# amp_pt2322_v_1_0.net
KiCad netlist of a schematic drawn in EAGLE
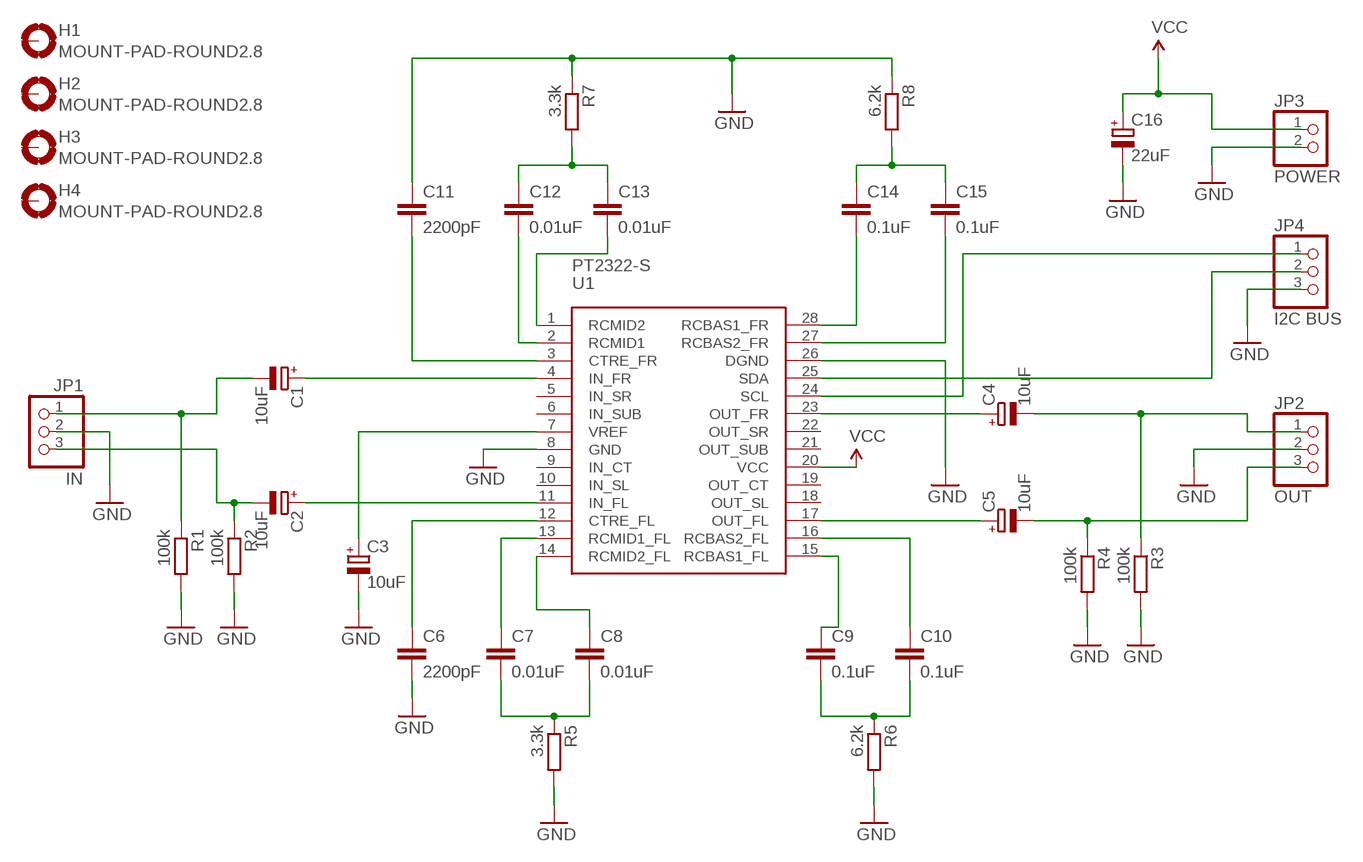
[diagram p0: schematic, sheet 1]

(export (version "E")
  (design (tool "Eeschema 10.0.6"))
  (components
    (comp (ref "C1")
      (value "10uF")
      (footprint "eagle-import:SMC_B")
      (libsource (lib "eagle-import") (part "CPOL-EUSMCB"))
    )
    (comp (ref "C2")
      (value "10uF")
      (footprint "eagle-import:SMC_B")
      (libsource (lib "eagle-import") (part "CPOL-EUSMCB"))
    )
    (comp (ref "C3")
      (value "10uF")
      (footprint "eagle-import:SMC_B")
      (libsource (lib "eagle-import") (part "CPOL-EUSMCB"))
    )
    (comp (ref "C4")
      (value "10uF")
      (footprint "eagle-import:SMC_B")
      (libsource (lib "eagle-import") (part "CPOL-EUSMCB"))
    )
    (comp (ref "C5")
      (value "10uF")
      (footprint "eagle-import:SMC_B")
      (libsource (lib "eagle-import") (part "CPOL-EUSMCB"))
    )
    (comp (ref "C6")
      (value "2200pF")
      (footprint "eagle-import:C0805K")
      (libsource (lib "eagle-import") (part "C-EUC0805K"))
    )
    (comp (ref "C7")
      (value "0.01uF")
      (footprint "eagle-import:C0805K")
      (libsource (lib "eagle-import") (part "C-EUC0805K"))
    )
    (comp (ref "C8")
      (value "0.01uF")
      (footprint "eagle-import:C0805K")
      (libsource (lib "eagle-import") (part "C-EUC0805K"))
    )
    (comp (ref "C9")
      (value "0.1uF")
      (footprint "eagle-import:C0805K")
      (libsource (lib "eagle-import") (part "C-EUC0805K"))
    )
    (comp (ref "C10")
      (value "0.1uF")
      (footprint "eagle-import:C0805K")
      (libsource (lib "eagle-import") (part "C-EUC0805K"))
    )
    (comp (ref "C11")
      (value "2200pF")
      (footprint "eagle-import:C0805K")
      (libsource (lib "eagle-import") (part "C-EUC0805K"))
    )
    (comp (ref "C12")
      (value "0.01uF")
      (footprint "eagle-import:C0805K")
      (libsource (lib "eagle-import") (part "C-EUC0805K"))
    )
    (comp (ref "C13")
      (value "0.01uF")
      (footprint "eagle-import:C0805K")
      (libsource (lib "eagle-import") (part "C-EUC0805K"))
    )
    (comp (ref "C14")
      (value "0.1uF")
      (footprint "eagle-import:C0805K")
      (libsource (lib "eagle-import") (part "C-EUC0805K"))
    )
    (comp (ref "C15")
      (value "0.1uF")
      (footprint "eagle-import:C0805K")
      (libsource (lib "eagle-import") (part "C-EUC0805K"))
    )
    (comp (ref "C16")
      (value "22uF")
      (footprint "eagle-import:SMC_B")
      (libsource (lib "eagle-import") (part "CPOL-EUSMCB"))
    )
    (comp (ref "H1")
      (value "MOUNT-PAD-ROUND2.8")
      (footprint "eagle-import:2,8-PAD")
      (libsource (lib "eagle-import") (part "MOUNT-PAD-ROUND2.8"))
    )
    (comp (ref "H2")
      (value "MOUNT-PAD-ROUND2.8")
      (footprint "eagle-import:2,8-PAD")
      (libsource (lib "eagle-import") (part "MOUNT-PAD-ROUND2.8"))
    )
    (comp (ref "H3")
      (value "MOUNT-PAD-ROUND2.8")
      (footprint "eagle-import:2,8-PAD")
      (libsource (lib "eagle-import") (part "MOUNT-PAD-ROUND2.8"))
    )
    (comp (ref "H4")
      (value "MOUNT-PAD-ROUND2.8")
      (footprint "eagle-import:2,8-PAD")
      (libsource (lib "eagle-import") (part "MOUNT-PAD-ROUND2.8"))
    )
    (comp (ref "JP1")
      (value "IN")
      (footprint "eagle-import:1X03")
      (libsource (lib "eagle-import") (part "PINHD-1X3"))
    )
    (comp (ref "JP2")
      (value "OUT")
      (footprint "eagle-import:1X03")
      (libsource (lib "eagle-import") (part "PINHD-1X3"))
    )
    (comp (ref "JP3")
      (value "POWER")
      (footprint "eagle-import:1X02")
      (libsource (lib "eagle-import") (part "PINHD-1X2"))
    )
    (comp (ref "JP4")
      (value "I2C BUS")
      (footprint "eagle-import:1X03")
      (libsource (lib "eagle-import") (part "PINHD-1X3"))
    )
    (comp (ref "R1")
      (value "100k")
      (footprint "eagle-import:R0805")
      (libsource (lib "eagle-import") (part "R-EU_R0805"))
    )
    (comp (ref "R2")
      (value "100k")
      (footprint "eagle-import:R0805")
      (libsource (lib "eagle-import") (part "R-EU_R0805"))
    )
    (comp (ref "R3")
      (value "100k")
      (footprint "eagle-import:R0805")
      (libsource (lib "eagle-import") (part "R-EU_R0805"))
    )
    (comp (ref "R4")
      (value "100k")
      (footprint "eagle-import:R0805")
      (libsource (lib "eagle-import") (part "R-EU_R0805"))
    )
    (comp (ref "R5")
      (value "3.3k")
      (footprint "eagle-import:R0805")
      (libsource (lib "eagle-import") (part "R-EU_R0805"))
    )
    (comp (ref "R6")
      (value "6.2k")
      (footprint "eagle-import:R0805")
      (libsource (lib "eagle-import") (part "R-EU_R0805"))
    )
    (comp (ref "R7")
      (value "3.3k")
      (footprint "eagle-import:R0805")
      (libsource (lib "eagle-import") (part "R-EU_R0805"))
    )
    (comp (ref "R8")
      (value "6.2k")
      (footprint "eagle-import:R0805")
      (libsource (lib "eagle-import") (part "R-EU_R0805"))
    )
    (comp (ref "U1")
      (value "PT2322-S")
      (footprint "eagle-import:SOP28")
      (libsource (lib "eagle-import") (part "PT2322-S"))
    )
  )
  (nets
    (net (code "1") (name "GND") (class "Default")
      (node (ref "C11") (pin "1") (pinfunction "1_1") (pintype "passive"))
      (node (ref "C16") (pin "-") (pinfunction "-_-") (pintype "passive"))
      (node (ref "C3") (pin "-") (pinfunction "-_-") (pintype "passive"))
      (node (ref "C6") (pin "2") (pinfunction "2_2") (pintype "passive"))
      (node (ref "JP1") (pin "2") (pinfunction "2_2") (pintype "passive"))
      (node (ref "JP2") (pin "2") (pinfunction "2_2") (pintype "passive"))
      (node (ref "JP3") (pin "2") (pinfunction "2_2") (pintype "passive"))
      (node (ref "JP4") (pin "3") (pinfunction "3_3") (pintype "passive"))
      (node (ref "R1") (pin "2") (pinfunction "2_2") (pintype "passive"))
      (node (ref "R2") (pin "2") (pinfunction "2_2") (pintype "passive"))
      (node (ref "R3") (pin "2") (pinfunction "2_2") (pintype "passive"))
      (node (ref "R4") (pin "2") (pinfunction "2_2") (pintype "passive"))
      (node (ref "R5") (pin "2") (pinfunction "2_2") (pintype "passive"))
      (node (ref "R6") (pin "2") (pinfunction "2_2") (pintype "passive"))
      (node (ref "R7") (pin "1") (pinfunction "1_1") (pintype "passive"))
      (node (ref "R8") (pin "1") (pinfunction "1_1") (pintype "passive"))
      (node (ref "U1") (pin "26") (pinfunction "DGND_26") (pintype "power_in"))
      (node (ref "U1") (pin "8") (pinfunction "GND_8") (pintype "power_in"))
    )
    (net (code "2") (name "Net-(C1-Pad-)") (class "Default")
      (node (ref "C1") (pin "-") (pinfunction "-_-") (pintype "passive"))
      (node (ref "JP1") (pin "1") (pinfunction "1_1") (pintype "passive"))
      (node (ref "R1") (pin "1") (pinfunction "1_1") (pintype "passive"))
    )
    (net (code "3") (name "Net-(C2-Pad-)") (class "Default")
      (node (ref "C2") (pin "-") (pinfunction "-_-") (pintype "passive"))
      (node (ref "JP1") (pin "3") (pinfunction "3_3") (pintype "passive"))
      (node (ref "R2") (pin "1") (pinfunction "1_1") (pintype "passive"))
    )
    (net (code "4") (name "Net-(C4-Pad-)") (class "Default")
      (node (ref "C4") (pin "-") (pinfunction "-_-") (pintype "passive"))
      (node (ref "JP2") (pin "1") (pinfunction "1_1") (pintype "passive"))
      (node (ref "R3") (pin "1") (pinfunction "1_1") (pintype "passive"))
    )
    (net (code "5") (name "Net-(C5-Pad-)") (class "Default")
      (node (ref "C5") (pin "-") (pinfunction "-_-") (pintype "passive"))
      (node (ref "JP2") (pin "3") (pinfunction "3_3") (pintype "passive"))
      (node (ref "R4") (pin "1") (pinfunction "1_1") (pintype "passive"))
    )
    (net (code "6") (name "Net-(C7-Pad2)") (class "Default")
      (node (ref "C7") (pin "2") (pinfunction "2_2") (pintype "passive"))
      (node (ref "C8") (pin "2") (pinfunction "2_2") (pintype "passive"))
      (node (ref "R5") (pin "1") (pinfunction "1_1") (pintype "passive"))
    )
    (net (code "7") (name "Net-(C10-Pad2)") (class "Default")
      (node (ref "C10") (pin "2") (pinfunction "2_2") (pintype "passive"))
      (node (ref "C9") (pin "2") (pinfunction "2_2") (pintype "passive"))
      (node (ref "R6") (pin "1") (pinfunction "1_1") (pintype "passive"))
    )
    (net (code "8") (name "Net-(C12-Pad1)") (class "Default")
      (node (ref "C12") (pin "1") (pinfunction "1_1") (pintype "passive"))
      (node (ref "C13") (pin "1") (pinfunction "1_1") (pintype "passive"))
      (node (ref "R7") (pin "2") (pinfunction "2_2") (pintype "passive"))
    )
    (net (code "9") (name "Net-(C14-Pad1)") (class "Default")
      (node (ref "C14") (pin "1") (pinfunction "1_1") (pintype "passive"))
      (node (ref "C15") (pin "1") (pinfunction "1_1") (pintype "passive"))
      (node (ref "R8") (pin "2") (pinfunction "2_2") (pintype "passive"))
    )
    (net (code "10") (name "Net-(U1-CTRE_FL)") (class "Default")
      (node (ref "C6") (pin "1") (pinfunction "1_1") (pintype "passive"))
      (node (ref "U1") (pin "12") (pinfunction "CTRE_FL_12") (pintype "bidirectional"))
    )
    (net (code "11") (name "Net-(U1-CTRE_FR)") (class "Default")
      (node (ref "C11") (pin "2") (pinfunction "2_2") (pintype "passive"))
      (node (ref "U1") (pin "3") (pinfunction "CTRE_FR_3") (pintype "bidirectional"))
    )
    (net (code "12") (name "Net-(U1-IN_FL)") (class "Default")
      (node (ref "C2") (pin "+") (pinfunction "+_+") (pintype "passive"))
      (node (ref "U1") (pin "11") (pinfunction "IN_FL_11") (pintype "input"))
    )
    (net (code "13") (name "Net-(U1-IN_FR)") (class "Default")
      (node (ref "C1") (pin "+") (pinfunction "+_+") (pintype "passive"))
      (node (ref "U1") (pin "4") (pinfunction "IN_FR_4") (pintype "input"))
    )
    (net (code "14") (name "Net-(U1-OUT_FL)") (class "Default")
      (node (ref "C5") (pin "+") (pinfunction "+_+") (pintype "passive"))
      (node (ref "U1") (pin "17") (pinfunction "OUT_FL_17") (pintype "output"))
    )
    (net (code "15") (name "Net-(U1-OUT_FR)") (class "Default")
      (node (ref "C4") (pin "+") (pinfunction "+_+") (pintype "passive"))
      (node (ref "U1") (pin "23") (pinfunction "OUT_FR_23") (pintype "output"))
    )
    (net (code "16") (name "Net-(U1-RCBAS1_FL)") (class "Default")
      (node (ref "C9") (pin "1") (pinfunction "1_1") (pintype "passive"))
      (node (ref "U1") (pin "15") (pinfunction "RCBAS1_FL_15") (pintype "bidirectional"))
    )
    (net (code "17") (name "Net-(U1-RCBAS1_FR)") (class "Default")
      (node (ref "C14") (pin "2") (pinfunction "2_2") (pintype "passive"))
      (node (ref "U1") (pin "28") (pinfunction "RCBAS1_FR_28") (pintype "bidirectional"))
    )
    (net (code "18") (name "Net-(U1-RCBAS2_FL)") (class "Default")
      (node (ref "C10") (pin "1") (pinfunction "1_1") (pintype "passive"))
      (node (ref "U1") (pin "16") (pinfunction "RCBAS2_FL_16") (pintype "bidirectional"))
    )
    (net (code "19") (name "Net-(U1-RCBAS2_FR)") (class "Default")
      (node (ref "C15") (pin "2") (pinfunction "2_2") (pintype "passive"))
      (node (ref "U1") (pin "27") (pinfunction "RCBAS2_FR_27") (pintype "bidirectional"))
    )
    (net (code "20") (name "Net-(U1-RCMID1)") (class "Default")
      (node (ref "C12") (pin "2") (pinfunction "2_2") (pintype "passive"))
      (node (ref "U1") (pin "2") (pinfunction "RCMID1_2") (pintype "bidirectional"))
    )
    (net (code "21") (name "Net-(U1-RCMID1_FL)") (class "Default")
      (node (ref "C7") (pin "1") (pinfunction "1_1") (pintype "passive"))
      (node (ref "U1") (pin "13") (pinfunction "RCMID1_FL_13") (pintype "bidirectional"))
    )
    (net (code "22") (name "Net-(U1-RCMID2)") (class "Default")
      (node (ref "C13") (pin "2") (pinfunction "2_2") (pintype "passive"))
      (node (ref "U1") (pin "1") (pinfunction "RCMID2_1") (pintype "bidirectional"))
    )
    (net (code "23") (name "Net-(U1-RCMID2_FL)") (class "Default")
      (node (ref "C8") (pin "1") (pinfunction "1_1") (pintype "passive"))
      (node (ref "U1") (pin "14") (pinfunction "RCMID2_FL_14") (pintype "bidirectional"))
    )
    (net (code "24") (name "Net-(U1-SCL)") (class "Default")
      (node (ref "JP4") (pin "1") (pinfunction "1_1") (pintype "passive"))
      (node (ref "U1") (pin "24") (pinfunction "SCL_24") (pintype "bidirectional"))
    )
    (net (code "25") (name "Net-(U1-SDA)") (class "Default")
      (node (ref "JP4") (pin "2") (pinfunction "2_2") (pintype "passive"))
      (node (ref "U1") (pin "25") (pinfunction "SDA_25") (pintype "bidirectional"))
    )
    (net (code "26") (name "Net-(U1-VREF)") (class "Default")
      (node (ref "C3") (pin "+") (pinfunction "+_+") (pintype "passive"))
      (node (ref "U1") (pin "7") (pinfunction "VREF_7") (pintype "power_in"))
    )
    (net (code "27") (name "VCC") (class "Default")
      (node (ref "C16") (pin "+") (pinfunction "+_+") (pintype "passive"))
      (node (ref "JP3") (pin "1") (pinfunction "1_1") (pintype "passive"))
      (node (ref "U1") (pin "20") (pinfunction "VCC_20") (pintype "power_in"))
    )
    (net (code "28") (name "unconnected-(H1-MOUNT-PadB2,8)") (class "Default")
      (node (ref "H1") (pin "B2,8") (pinfunction "MOUNT_B2,8") (pintype "passive"))
    )
    (net (code "29") (name "unconnected-(H2-MOUNT-PadB2,8)") (class "Default")
      (node (ref "H2") (pin "B2,8") (pinfunction "MOUNT_B2,8") (pintype "passive"))
    )
    (net (code "30") (name "unconnected-(H3-MOUNT-PadB2,8)") (class "Default")
      (node (ref "H3") (pin "B2,8") (pinfunction "MOUNT_B2,8") (pintype "passive"))
    )
    (net (code "31") (name "unconnected-(H4-MOUNT-PadB2,8)") (class "Default")
      (node (ref "H4") (pin "B2,8") (pinfunction "MOUNT_B2,8") (pintype "passive"))
    )
    (net (code "32") (name "unconnected-(U1-IN_CT-Pad9)") (class "Default")
      (node (ref "U1") (pin "9") (pinfunction "IN_CT_9") (pintype "input"))
    )
    (net (code "33") (name "unconnected-(U1-IN_SL-Pad10)") (class "Default")
      (node (ref "U1") (pin "10") (pinfunction "IN_SL_10") (pintype "input"))
    )
    (net (code "34") (name "unconnected-(U1-IN_SR-Pad5)") (class "Default")
      (node (ref "U1") (pin "5") (pinfunction "IN_SR_5") (pintype "input"))
    )
    (net (code "35") (name "unconnected-(U1-IN_SUB-Pad6)") (class "Default")
      (node (ref "U1") (pin "6") (pinfunction "IN_SUB_6") (pintype "input"))
    )
    (net (code "36") (name "unconnected-(U1-OUT_CT-Pad19)") (class "Default")
      (node (ref "U1") (pin "19") (pinfunction "OUT_CT_19") (pintype "output"))
    )
    (net (code "37") (name "unconnected-(U1-OUT_SL-Pad18)") (class "Default")
      (node (ref "U1") (pin "18") (pinfunction "OUT_SL_18") (pintype "output"))
    )
    (net (code "38") (name "unconnected-(U1-OUT_SR-Pad22)") (class "Default")
      (node (ref "U1") (pin "22") (pinfunction "OUT_SR_22") (pintype "output"))
    )
    (net (code "39") (name "unconnected-(U1-OUT_SUB-Pad21)") (class "Default")
      (node (ref "U1") (pin "21") (pinfunction "OUT_SUB_21") (pintype "output"))
    )
  )
)
